# Power.net
KiCad netlist of a schematic drawn in Altium Designer
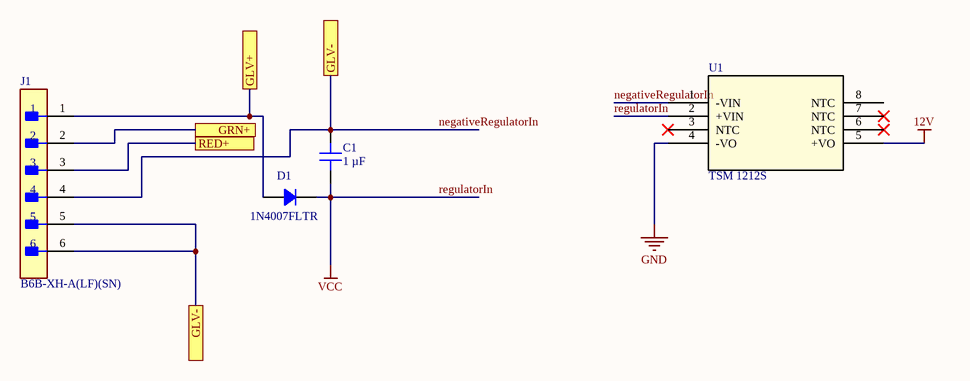
[diagram p0: Power.SchDoc]

(export (version "E")
  (design (tool "Eeschema 10.0.6"))
  (components
    (comp (ref "C1")
      (value "1 µF")
      (footprint "CAP 0805_2012")
      (description "CAP CER 1UF 50V X7R 0805")
      (fields
        (field (name "PART NUMBER") "GCJ21BR71H105KA01L")
        (field (name "MANUFACTURER") "Murata Electronics")
      )
      (libsource (lib "Celestial Altium Library - altium_library") (part "Capacitor"))
    )
    (comp (ref "D1")
      (value "1N4007FLTR")
      (footprint "SOD123F")
      (description "STANDARD RECTIFIER 1000V SOD-123")
      (fields (field (name "MANUFACTURER") "SMC Diode Solutions"))
      (libsource (lib "Celestial Altium Library - altium_library") (part "Diode"))
    )
    (comp (ref "J1")
      (value "B6B-XH-A(LF)(SN)")
      (footprint "FP-B6B-XH-A_LF_SN-MFG")
      (description "CONN HEADER VERT 6POS 2.5MM")
      (libsource (lib "Altium Content Vault") (part "f2cb566baf1c37ab5a3b8e90bbeafd6"))
    )
    (comp (ref "U1")
      (value "TSM 1212S")
      (footprint "TSM_SINGLE_TRP")
      (description "No Description Available")
      (fields (field (name "COPYRIGHT") "Copyright (C) 2024 Ultra Librarian. All rights reserved."))
      (libsource (lib "TSM1212S") (part "TSM 1212S"))
    )
  )
  (nets
    (net (code "1") (name "/GLV+") (class "Default")
      (node (ref "D1") (pin "1") (pinfunction "1_1") (pintype "passive"))
      (node (ref "J1") (pin "1") (pinfunction "1_1") (pintype "passive"))
    )
    (net (code "2") (name "/GRN+") (class "Default")
      (node (ref "J1") (pin "2") (pinfunction "2_2") (pintype "passive"))
    )
    (net (code "3") (name "/RED+") (class "Default")
      (node (ref "J1") (pin "3") (pinfunction "3_3") (pintype "passive"))
    )
    (net (code "4") (name "/negativeRegulatorIn") (class "Default")
      (node (ref "C1") (pin "2") (pinfunction "2_2") (pintype "passive"))
      (node (ref "J1") (pin "4") (pinfunction "4_4") (pintype "passive"))
      (node (ref "J1") (pin "5") (pinfunction "5_5") (pintype "passive"))
      (node (ref "J1") (pin "6") (pinfunction "6_6") (pintype "passive"))
      (node (ref "U1") (pin "1") (pinfunction "-VIN_1") (pintype "power_in"))
    )
    (net (code "5") (name "12V") (class "Default")
      (node (ref "U1") (pin "5") (pinfunction "+VO_5") (pintype "power_in"))
    )
    (net (code "6") (name "GND") (class "Default")
      (node (ref "U1") (pin "4") (pinfunction "-VO_4") (pintype "power_in"))
    )
    (net (code "7") (name "VCC") (class "Default")
      (node (ref "C1") (pin "1") (pinfunction "1_1") (pintype "passive"))
      (node (ref "D1") (pin "2") (pinfunction "2_2") (pintype "passive"))
      (node (ref "U1") (pin "2") (pinfunction "+VIN_2") (pintype "power_in"))
    )
    (net (code "8") (name "unconnected-(U1-NTC-Pad3)") (class "Default")
      (node (ref "U1") (pin "3") (pinfunction "NTC_3") (pintype "passive+no_connect"))
    )
    (net (code "9") (name "unconnected-(U1-NTC-Pad6)") (class "Default")
      (node (ref "U1") (pin "6") (pinfunction "NTC_6") (pintype "passive+no_connect"))
    )
    (net (code "10") (name "unconnected-(U1-NTC-Pad7)") (class "Default")
      (node (ref "U1") (pin "7") (pinfunction "NTC_7") (pintype "passive+no_connect"))
    )
    (net (code "11") (name "unconnected-(U1-NTC-Pad8)") (class "Default")
      (node (ref "U1") (pin "8") (pinfunction "NTC_8") (pintype "passive"))
    )
  )
)
